# TSL25911-Breakout_v10.net
KiCad netlist of a schematic drawn in EAGLE
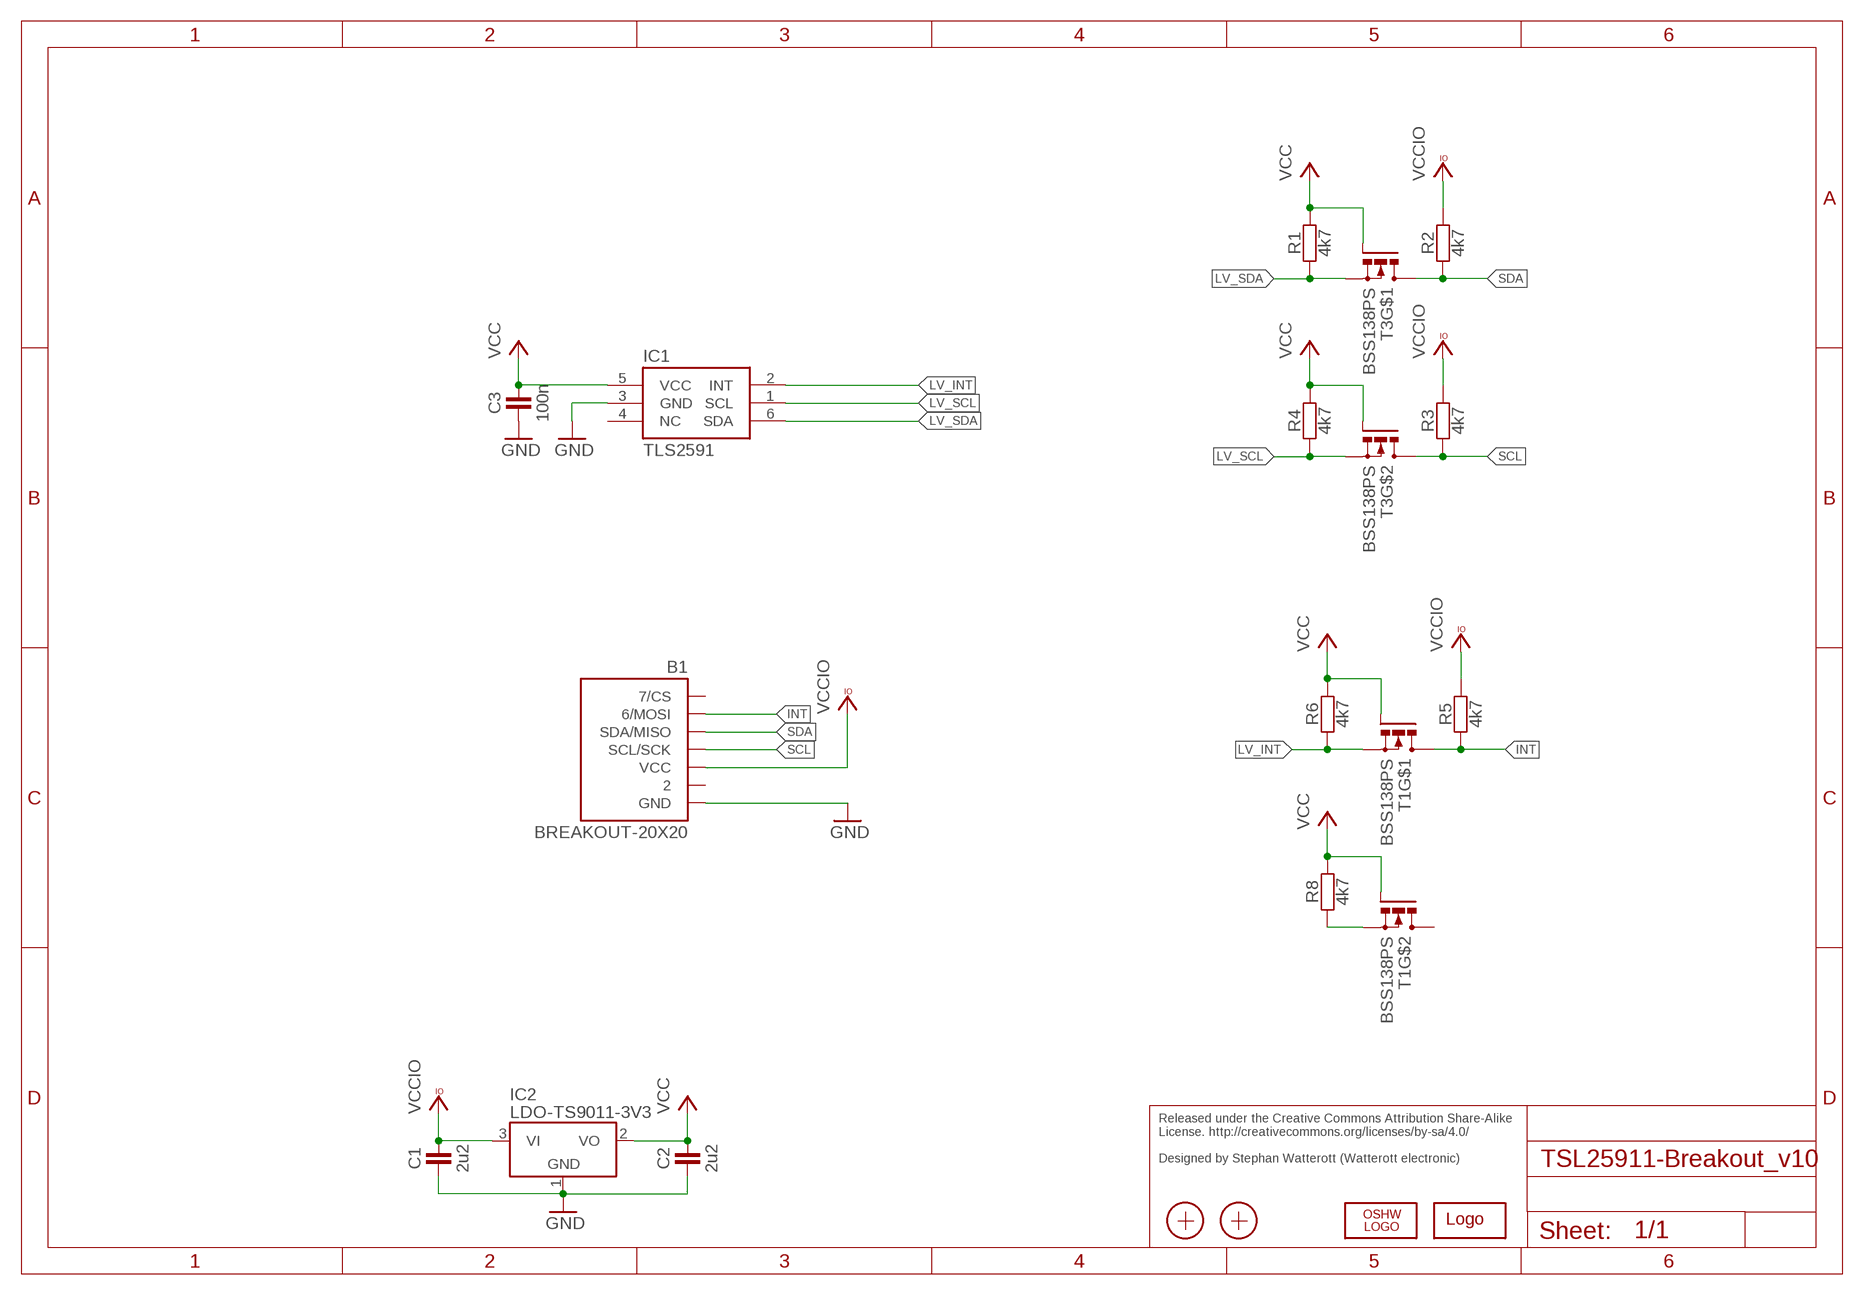
[diagram p0: schematic, sheet 1]

(export (version "E")
  (design (tool "Eeschema 10.0.6"))
  (components
    (comp (ref "B1")
      (value "BREAKOUT-20X20")
      (footprint "eagle-import:BREAKOUT-20X20")
      (libsource (lib "eagle-import") (part "BREAKOUT-20X20"))
    )
    (comp (ref "C1")
      (value "2u2")
      (footprint "eagle-import:R0402")
      (libsource (lib "eagle-import") (part "CAPACITOR-C0402"))
    )
    (comp (ref "C2")
      (value "2u2")
      (footprint "eagle-import:R0402")
      (libsource (lib "eagle-import") (part "CAPACITOR-C0402"))
    )
    (comp (ref "C3")
      (value "100n")
      (footprint "eagle-import:R0402")
      (libsource (lib "eagle-import") (part "CAPACITOR-C0402"))
    )
    (comp (ref "IC1")
      (value "TLS2591")
      (footprint "eagle-import:WFDFN6")
      (libsource (lib "eagle-import") (part "TLS2591"))
    )
    (comp (ref "IC2")
      (value "LDO-TS9011-3V3")
      (footprint "eagle-import:SOT23")
      (libsource (lib "eagle-import") (part "LDO-TS9011-3V3"))
    )
    (comp (ref "LOGO1")
      (value "LOGO-S_PLACE_M")
      (footprint "eagle-import:SPARK_TPLACE_M")
      (libsource (lib "eagle-import") (part "LOGO-S_PLACE_M"))
    )
    (comp (ref "LOGO2")
      (value "OSHW_LOGOX0070")
      (footprint "eagle-import:OSHW_6X70")
      (libsource (lib "eagle-import") (part "OSHW_LOGOX0070"))
    )
    (comp (ref "R1")
      (value "4k7")
      (footprint "eagle-import:R0402")
      (libsource (lib "eagle-import") (part "RESISTOR-R0402"))
    )
    (comp (ref "R2")
      (value "4k7")
      (footprint "eagle-import:R0402")
      (libsource (lib "eagle-import") (part "RESISTOR-R0402"))
    )
    (comp (ref "R3")
      (value "4k7")
      (footprint "eagle-import:R0402")
      (libsource (lib "eagle-import") (part "RESISTOR-R0402"))
    )
    (comp (ref "R4")
      (value "4k7")
      (footprint "eagle-import:R0402")
      (libsource (lib "eagle-import") (part "RESISTOR-R0402"))
    )
    (comp (ref "R5")
      (value "4k7")
      (footprint "eagle-import:R0402")
      (libsource (lib "eagle-import") (part "RESISTOR-R0402"))
    )
    (comp (ref "R6")
      (value "4k7")
      (footprint "eagle-import:R0402")
      (libsource (lib "eagle-import") (part "RESISTOR-R0402"))
    )
    (comp (ref "R8")
      (value "4k7")
      (footprint "eagle-import:R0402")
      (libsource (lib "eagle-import") (part "RESISTOR-R0402"))
    )
    (comp (ref "T1")
      (value "BSS138PS")
      (footprint "eagle-import:SOT363")
      (libsource (lib "eagle-import") (part "BSS138PS"))
    )
    (comp (ref "T3")
      (value "BSS138PS")
      (footprint "eagle-import:SOT363")
      (libsource (lib "eagle-import") (part "BSS138PS"))
    )
    (comp (ref "X1")
      (value "PASSER-07")
      (footprint "eagle-import:PASSER_07MM")
      (libsource (lib "eagle-import") (part "PASSER-07"))
    )
    (comp (ref "X2")
      (value "PASSER-07")
      (footprint "eagle-import:PASSER_07MM")
      (libsource (lib "eagle-import") (part "PASSER-07"))
    )
  )
  (nets
    (net (code "1") (name "GND") (class "Default")
      (node (ref "B1") (pin "GND") (pinfunction "GND_GND") (pintype "power_in"))
      (node (ref "C1") (pin "1") (pinfunction "1_1") (pintype "passive"))
      (node (ref "C2") (pin "1") (pinfunction "1_1") (pintype "passive"))
      (node (ref "C3") (pin "1") (pinfunction "1_1") (pintype "passive"))
      (node (ref "IC1") (pin "3") (pinfunction "GND_3") (pintype "power_in"))
      (node (ref "IC2") (pin "1") (pinfunction "GND_1") (pintype "passive"))
    )
    (net (code "2") (name "INT") (class "Default")
      (node (ref "B1") (pin "MOSI") (pinfunction "6/MOSI_MOSI") (pintype "bidirectional"))
      (node (ref "R5") (pin "1") (pinfunction "1_1") (pintype "passive"))
      (node (ref "T1") (pin "6") (pinfunction "D_6") (pintype "passive"))
    )
    (net (code "3") (name "LV_INT") (class "Default")
      (node (ref "IC1") (pin "2") (pinfunction "INT_2") (pintype "open_collector"))
      (node (ref "R6") (pin "1") (pinfunction "1_1") (pintype "passive"))
      (node (ref "T1") (pin "1") (pinfunction "S_1") (pintype "passive"))
    )
    (net (code "4") (name "LV_SCL") (class "Default")
      (node (ref "IC1") (pin "1") (pinfunction "SCL_1") (pintype "input"))
      (node (ref "R4") (pin "1") (pinfunction "1_1") (pintype "passive"))
      (node (ref "T3") (pin "4") (pinfunction "S_4") (pintype "passive"))
    )
    (net (code "5") (name "LV_SDA") (class "Default")
      (node (ref "IC1") (pin "6") (pinfunction "SDA_6") (pintype "output"))
      (node (ref "R1") (pin "1") (pinfunction "1_1") (pintype "passive"))
      (node (ref "T3") (pin "1") (pinfunction "S_1") (pintype "passive"))
    )
    (net (code "6") (name "Net-(T1B-S)") (class "Default")
      (node (ref "R8") (pin "1") (pinfunction "1_1") (pintype "passive"))
      (node (ref "T1") (pin "4") (pinfunction "S_4") (pintype "passive"))
    )
    (net (code "7") (name "SCL") (class "Default")
      (node (ref "B1") (pin "SCL/SCK") (pinfunction "SCL/SCK_SCL/SCK") (pintype "bidirectional"))
      (node (ref "R3") (pin "1") (pinfunction "1_1") (pintype "passive"))
      (node (ref "T3") (pin "3") (pinfunction "D_3") (pintype "passive"))
    )
    (net (code "8") (name "SDA") (class "Default")
      (node (ref "B1") (pin "SDA/MISO") (pinfunction "SDA/MISO_SDA/MISO") (pintype "bidirectional"))
      (node (ref "R2") (pin "1") (pinfunction "1_1") (pintype "passive"))
      (node (ref "T3") (pin "6") (pinfunction "D_6") (pintype "passive"))
    )
    (net (code "9") (name "VCC") (class "Default")
      (node (ref "C2") (pin "2") (pinfunction "2_2") (pintype "passive"))
      (node (ref "C3") (pin "2") (pinfunction "2_2") (pintype "passive"))
      (node (ref "IC1") (pin "5") (pinfunction "VCC_5") (pintype "power_in"))
      (node (ref "IC2") (pin "2") (pinfunction "VO_2") (pintype "passive"))
      (node (ref "R1") (pin "2") (pinfunction "2_2") (pintype "passive"))
      (node (ref "R4") (pin "2") (pinfunction "2_2") (pintype "passive"))
      (node (ref "R6") (pin "2") (pinfunction "2_2") (pintype "passive"))
      (node (ref "R8") (pin "2") (pinfunction "2_2") (pintype "passive"))
      (node (ref "T1") (pin "2") (pinfunction "G_2") (pintype "passive"))
      (node (ref "T1") (pin "5") (pinfunction "G_5") (pintype "passive"))
      (node (ref "T3") (pin "2") (pinfunction "G_2") (pintype "passive"))
      (node (ref "T3") (pin "5") (pinfunction "G_5") (pintype "passive"))
    )
    (net (code "10") (name "VCCIO") (class "Default")
      (node (ref "B1") (pin "VCC") (pinfunction "VCC_VCC") (pintype "power_in"))
      (node (ref "C1") (pin "2") (pinfunction "2_2") (pintype "passive"))
      (node (ref "IC2") (pin "3") (pinfunction "VI_3") (pintype "input"))
      (node (ref "R2") (pin "2") (pinfunction "2_2") (pintype "passive"))
      (node (ref "R3") (pin "2") (pinfunction "2_2") (pintype "passive"))
      (node (ref "R5") (pin "2") (pinfunction "2_2") (pintype "passive"))
    )
    (net (code "11") (name "unconnected-(B1-7{slash}CS-PadCS)") (class "Default")
      (node (ref "B1") (pin "CS") (pinfunction "7/CS_CS") (pintype "bidirectional"))
    )
    (net (code "12") (name "unconnected-(B1-Pad2)") (class "Default")
      (node (ref "B1") (pin "2") (pinfunction "2_2") (pintype "bidirectional"))
    )
    (net (code "13") (name "unconnected-(IC1-NC-Pad4)") (class "Default")
      (node (ref "IC1") (pin "4") (pinfunction "NC_4") (pintype "no_connect"))
    )
    (net (code "14") (name "unconnected-(T1B-D-Pad3)") (class "Default")
      (node (ref "T1") (pin "3") (pinfunction "D_3") (pintype "passive"))
    )
  )
)
